# other.net
KiCad netlist of a schematic drawn in Altium Designer
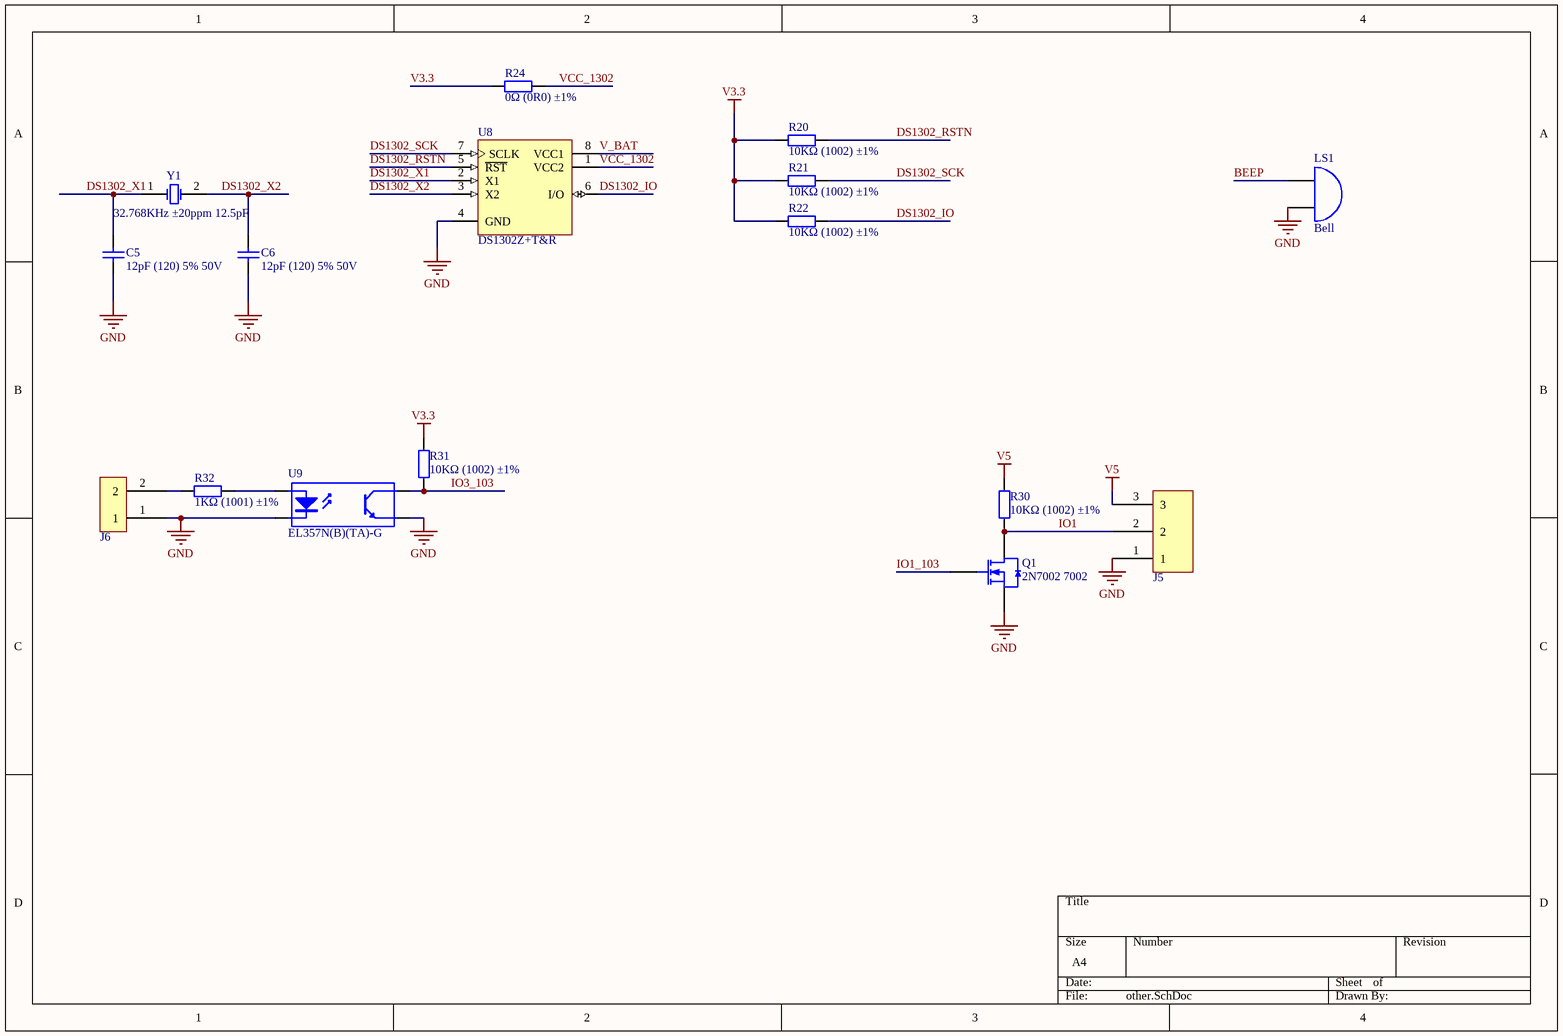
[diagram p0: other.SchDoc]

(export (version "E")
  (design (tool "Eeschema 10.0.6"))
  (components
    (comp (ref "C5")
      (value "12pF (120) 5% 50V")
      (footprint "0402_C")
      (description "贴片电容")
      (libsource (lib "Miscellaneous Devices LC") (part "0402 12pF (120) 5% 50V"))
    )
    (comp (ref "C6")
      (value "12pF (120) 5% 50V")
      (footprint "0402_C")
      (description "贴片电容")
      (libsource (lib "Miscellaneous Devices LC") (part "0402 12pF (120) 5% 50V"))
    )
    (comp (ref "J5") (value "KF301-3P") (footprint "KF301-3P") (libsource (lib "CHK-I") (part "KF301-3P")))
    (comp (ref "J6") (value "KF301-2P") (footprint "KF301-2P") (libsource (lib "CHK-I") (part "KF301-2P")))
    (comp (ref "LS1")
      (value "Bell")
      (footprint "PIN2")
      (description "Electrical Bell")
      (fields (field (name "PUBLISHER") "Altium Limited"))
      (libsource (lib "Miscellaneous Devices") (part "Bell"))
    )
    (comp (ref "Q1")
      (value "2N7002 7002")
      (footprint "SOT-23(SOT-23-3)")
      (description "MOS(场效应管)")
      (libsource (lib "Miscellaneous Devices LC") (part "2N7002 7002"))
    )
    (comp (ref "R20")
      (value "10KΩ (1002) ±1%")
      (footprint "0402_R")
      (description "贴片电阻")
      (libsource (lib "Miscellaneous Devices LC") (part "0402 10KΩ (1002) 1%"))
    )
    (comp (ref "R21")
      (value "10KΩ (1002) ±1%")
      (footprint "0402_R")
      (description "贴片电阻")
      (libsource (lib "Miscellaneous Devices LC") (part "0402 10KΩ (1002) 1%"))
    )
    (comp (ref "R22")
      (value "10KΩ (1002) ±1%")
      (footprint "0402_R")
      (description "贴片电阻")
      (libsource (lib "Miscellaneous Devices LC") (part "0402 10KΩ (1002) 1%"))
    )
    (comp (ref "R24")
      (value "0Ω (0R0) ±1%")
      (footprint "1206_R")
      (description "贴片电阻")
      (libsource (lib "Miscellaneous Devices LC") (part "1206 0Ω (0R0) 1%"))
    )
    (comp (ref "R30")
      (value "10KΩ (1002) ±1%")
      (footprint "1206_R")
      (description "贴片电阻")
      (libsource (lib "Miscellaneous Devices LC") (part "1206 10KΩ (1002) 1%"))
    )
    (comp (ref "R31")
      (value "10KΩ (1002) ±1%")
      (footprint "1206_R")
      (description "贴片电阻")
      (libsource (lib "Miscellaneous Devices LC") (part "1206 10KΩ (1002) 1%"))
    )
    (comp (ref "R32")
      (value "1KΩ (1001) ±1%")
      (footprint "1206_R")
      (description "贴片电阻")
      (libsource (lib "Miscellaneous Devices LC") (part "1206 1KΩ (1001) 1%"))
    )
    (comp (ref "U8")
      (value "DS1302Z+T&R")
      (footprint "SOIC-8_150mil")
      (description "实时时钟")
      (libsource (lib "Miscellaneous Devices LC") (part "DS1302Z+T&R_[C8959]"))
    )
    (comp (ref "U9")
      (value "EL357N(B)(TA)-G")
      (footprint "SOP-4_P2.54")
      (description "贴片光耦")
      (libsource (lib "Miscellaneous Devices LC") (part "EL357N(B)(TA)-G_[C6649]"))
    )
    (comp (ref "Y1")
      (value "32.768KHz ±20ppm 12.5pF")
      (footprint "SMD-3215_2P FC - 135")
      (description "贴片晶振")
      (libsource (lib "Miscellaneous Devices LC") (part "SMD-3215_2P 32.768KHz 20ppm 12.5pF"))
    )
  )
  (nets
    (net (code "1") (name "/BEEP") (class "Default")
      (node (ref "LS1") (pin "1") (pinfunction "A_1") (pintype "passive"))
    )
    (net (code "2") (name "/DS1302_IO") (class "Default")
      (node (ref "R22") (pin "2") (pinfunction "2_2") (pintype "passive"))
      (node (ref "U8") (pin "6") (pinfunction "I/O_6") (pintype "bidirectional"))
    )
    (net (code "3") (name "/DS1302_RSTN") (class "Default")
      (node (ref "R20") (pin "2") (pinfunction "2_2") (pintype "passive"))
      (node (ref "U8") (pin "5") (pinfunction "~{RST}_5") (pintype "input"))
    )
    (net (code "4") (name "/DS1302_SCK") (class "Default")
      (node (ref "R21") (pin "2") (pinfunction "2_2") (pintype "passive"))
      (node (ref "U8") (pin "7") (pinfunction "SCLK_7") (pintype "input"))
    )
    (net (code "5") (name "/DS1302_X1") (class "Default")
      (node (ref "C5") (pin "2") (pinfunction "2_2") (pintype "passive"))
      (node (ref "U8") (pin "2") (pinfunction "X1_2") (pintype "input"))
      (node (ref "Y1") (pin "1") (pinfunction "OSC1_1") (pintype "passive"))
    )
    (net (code "6") (name "/DS1302_X2") (class "Default")
      (node (ref "C6") (pin "2") (pinfunction "2_2") (pintype "passive"))
      (node (ref "U8") (pin "3") (pinfunction "X2_3") (pintype "input"))
      (node (ref "Y1") (pin "2") (pinfunction "OSC2_2") (pintype "passive"))
    )
    (net (code "7") (name "/IO1") (class "Default")
      (node (ref "J5") (pin "2") (pinfunction "2_2") (pintype "passive"))
      (node (ref "Q1") (pin "3") (pinfunction "D_3") (pintype "passive"))
      (node (ref "R30") (pin "1") (pinfunction "1_1") (pintype "passive"))
    )
    (net (code "8") (name "/IO1_103") (class "Default")
      (node (ref "Q1") (pin "1") (pinfunction "G_1") (pintype "passive"))
    )
    (net (code "9") (name "/IO3_103") (class "Default")
      (node (ref "R31") (pin "1") (pinfunction "1_1") (pintype "passive"))
      (node (ref "U9") (pin "4") (pinfunction "C_4") (pintype "passive"))
    )
    (net (code "10") (name "/VCC_1302") (class "Default")
      (node (ref "R24") (pin "2") (pinfunction "2_2") (pintype "passive"))
      (node (ref "U8") (pin "1") (pinfunction "VCC2_1") (pintype "power_in"))
    )
    (net (code "11") (name "/V_BAT") (class "Default")
      (node (ref "U8") (pin "8") (pinfunction "VCC1_8") (pintype "power_in"))
    )
    (net (code "12") (name "GND") (class "Default")
      (node (ref "C5") (pin "1") (pinfunction "1_1") (pintype "passive"))
      (node (ref "C6") (pin "1") (pinfunction "1_1") (pintype "passive"))
      (node (ref "J5") (pin "1") (pinfunction "1_1") (pintype "passive"))
      (node (ref "J6") (pin "1") (pinfunction "1_1") (pintype "passive"))
      (node (ref "LS1") (pin "2") (pinfunction "B_2") (pintype "passive"))
      (node (ref "Q1") (pin "2") (pinfunction "S_2") (pintype "passive"))
      (node (ref "U8") (pin "4") (pinfunction "GND_4") (pintype "power_in"))
      (node (ref "U9") (pin "2") (pinfunction "K_2") (pintype "passive"))
      (node (ref "U9") (pin "3") (pinfunction "E_3") (pintype "passive"))
    )
    (net (code "13") (name "Net-(J6-Pad2)") (class "Default")
      (node (ref "J6") (pin "2") (pinfunction "2_2") (pintype "passive"))
      (node (ref "R32") (pin "1") (pinfunction "1_1") (pintype "passive"))
    )
    (net (code "14") (name "Net-(U9-A)") (class "Default")
      (node (ref "R32") (pin "2") (pinfunction "2_2") (pintype "passive"))
      (node (ref "U9") (pin "1") (pinfunction "A_1") (pintype "passive"))
    )
    (net (code "15") (name "V3.3") (class "Default")
      (node (ref "R20") (pin "1") (pinfunction "1_1") (pintype "passive"))
      (node (ref "R21") (pin "1") (pinfunction "1_1") (pintype "passive"))
      (node (ref "R22") (pin "1") (pinfunction "1_1") (pintype "passive"))
      (node (ref "R24") (pin "1") (pinfunction "1_1") (pintype "passive"))
      (node (ref "R31") (pin "2") (pinfunction "2_2") (pintype "passive"))
    )
    (net (code "16") (name "V5") (class "Default")
      (node (ref "J5") (pin "3") (pinfunction "3_3") (pintype "passive"))
      (node (ref "R30") (pin "2") (pinfunction "2_2") (pintype "passive"))
    )
  )
)
